# Boost_Controller.net
KiCad netlist of a schematic drawn in EAGLE
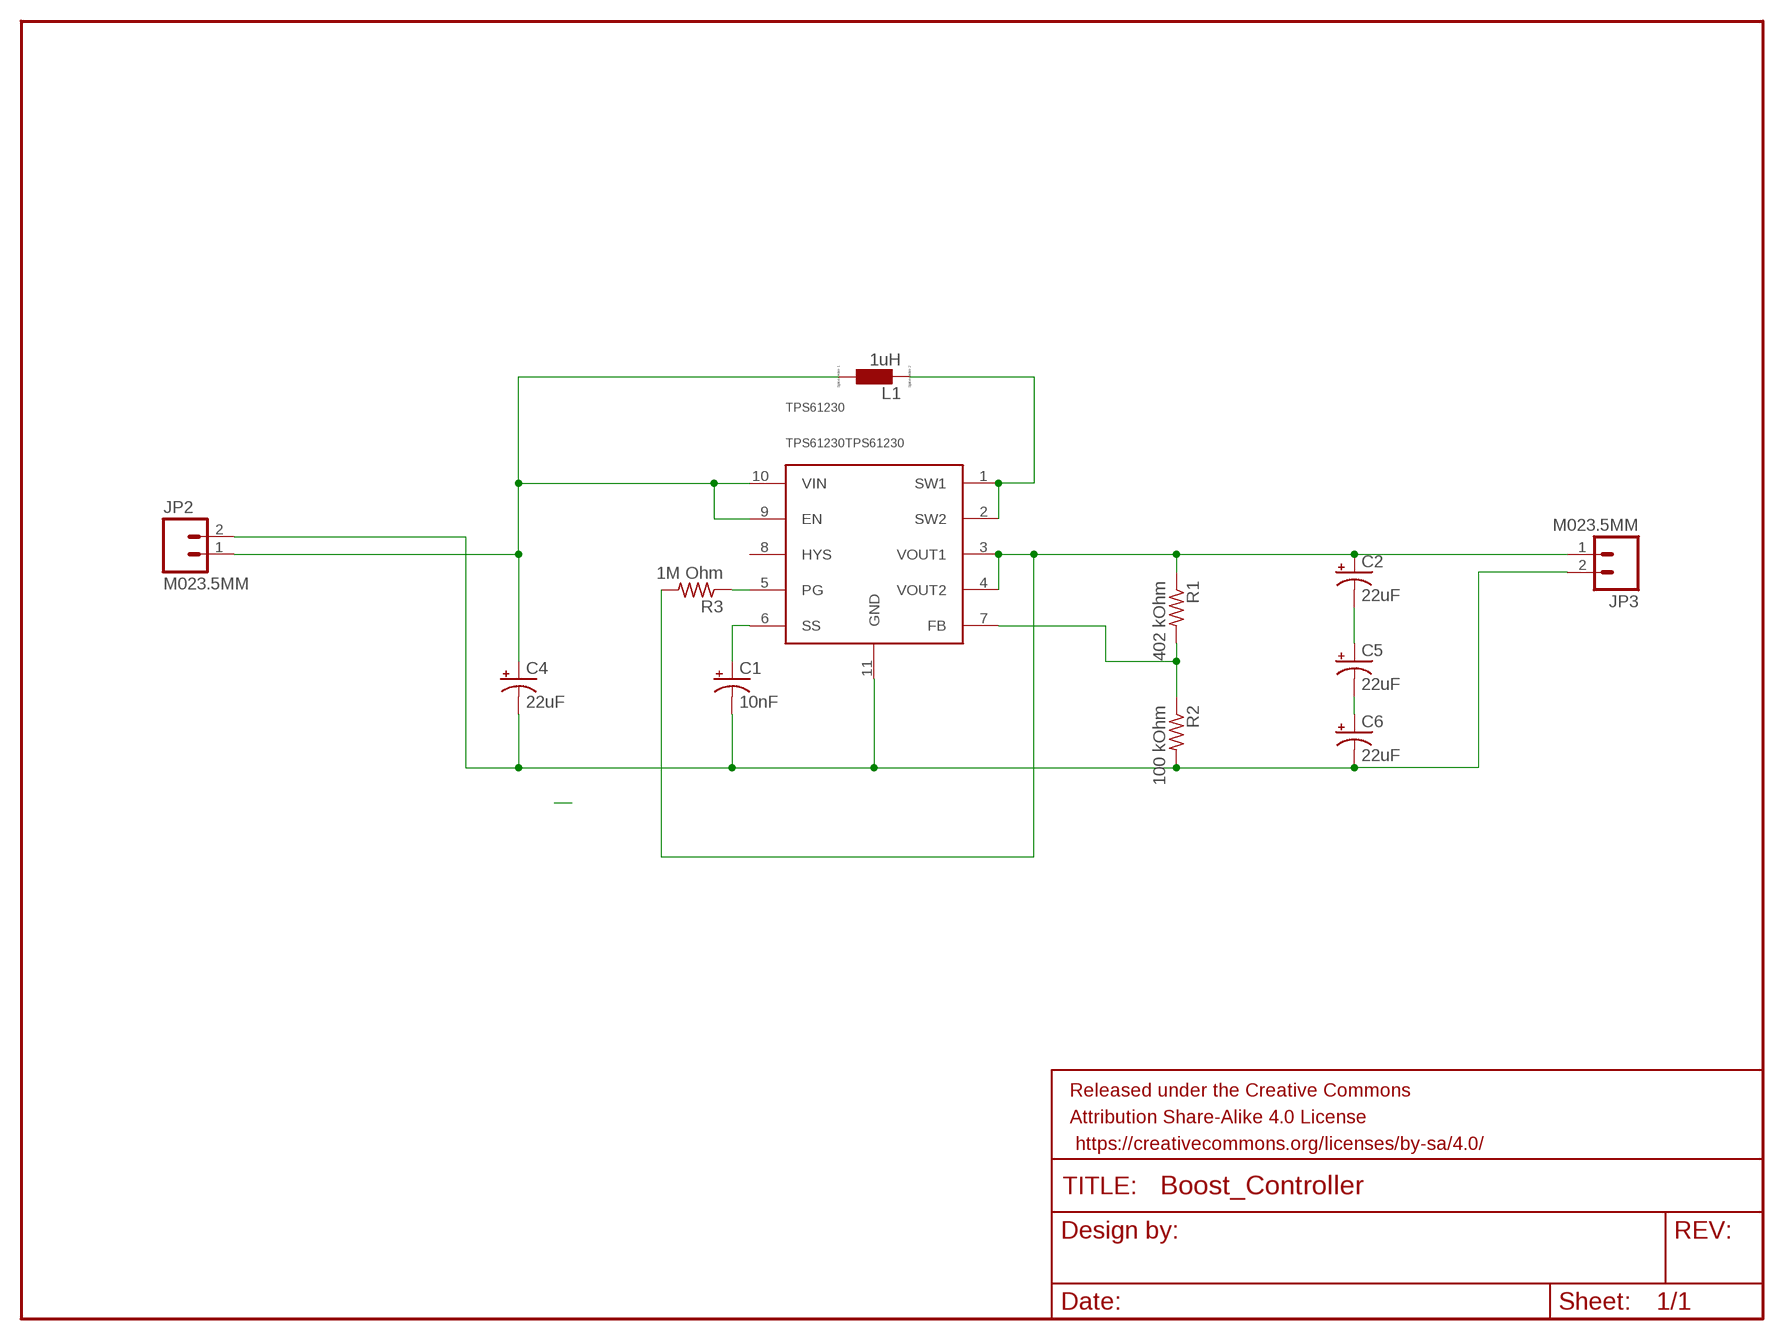
[diagram p0: schematic, sheet 1]

(export (version "E")
  (design (tool "Eeschema 10.0.6"))
  (components
    (comp (ref "C1")
      (value "10nF")
      (footprint "eagle-import:E2,5-5")
      (libsource (lib "eagle-import") (part "CPOL-USE2.5-5"))
    )
    (comp (ref "C2")
      (value "22uF")
      (footprint "eagle-import:E2,5-5")
      (libsource (lib "eagle-import") (part "CPOL-USE2.5-5"))
    )
    (comp (ref "C4")
      (value "22uF")
      (footprint "eagle-import:E2,5-5")
      (libsource (lib "eagle-import") (part "CPOL-USE2.5-5"))
    )
    (comp (ref "C5")
      (value "22uF")
      (footprint "eagle-import:E2,5-5")
      (libsource (lib "eagle-import") (part "CPOL-USE2.5-5"))
    )
    (comp (ref "C6")
      (value "22uF")
      (footprint "eagle-import:E2,5-5")
      (libsource (lib "eagle-import") (part "CPOL-USE2.5-5"))
    )
    (comp (ref "FRAME1")
      (value "FRAME-LETTER")
      (footprint "eagle-import:CREATIVE_COMMONS")
      (libsource (lib "eagle-import") (part "FRAME-LETTER"))
    )
    (comp (ref "JP2")
      (value "M023.5MM")
      (footprint "eagle-import:SCREWTERMINAL-3.5MM-2")
      (libsource (lib "eagle-import") (part "M023.5MM"))
    )
    (comp (ref "JP3")
      (value "M023.5MM")
      (footprint "eagle-import:SCREWTERMINAL-3.5MM-2")
      (libsource (lib "eagle-import") (part "M023.5MM"))
    )
    (comp (ref "L1")
      (value "1uH")
      (footprint "eagle-import:0207_10")
      (libsource (lib "eagle-import") (part "L0207/10"))
    )
    (comp (ref "R1")
      (value "402 kOhm")
      (footprint "eagle-import:0207_10")
      (libsource (lib "eagle-import") (part "R-US_0207/10"))
    )
    (comp (ref "R2")
      (value "100 kOhm")
      (footprint "eagle-import:0207_10")
      (libsource (lib "eagle-import") (part "R-US_0207/10"))
    )
    (comp (ref "R3")
      (value "1M Ohm")
      (footprint "eagle-import:0207_10")
      (libsource (lib "eagle-import") (part "R-US_0207/10"))
    )
    (comp (ref "TPS61230")
      (value "TPS61230TPS61230")
      (footprint "eagle-import:SON50P300X300X100-11N")
      (libsource (lib "eagle-import") (part "TPS61230TPS61230"))
    )
  )
  (nets
    (net (code "1") (name "Net-(C2-Pad-)") (class "Default")
      (node (ref "C2") (pin "-") (pinfunction "-_-") (pintype "passive"))
      (node (ref "C5") (pin "+") (pinfunction "+_+") (pintype "passive"))
    )
    (net (code "2") (name "Net-(C5-Pad-)") (class "Default")
      (node (ref "C5") (pin "-") (pinfunction "-_-") (pintype "passive"))
      (node (ref "C6") (pin "+") (pinfunction "+_+") (pintype "passive"))
    )
    (net (code "3") (name "Net-(TPS61230-EN)") (class "Default")
      (node (ref "C4") (pin "+") (pinfunction "+_+") (pintype "passive"))
      (node (ref "JP2") (pin "1") (pinfunction "1_1") (pintype "passive"))
      (node (ref "L1") (pin "1") (pinfunction "1_1") (pintype "passive"))
      (node (ref "TPS61230") (pin "10") (pinfunction "VIN_10") (pintype "bidirectional"))
      (node (ref "TPS61230") (pin "9") (pinfunction "EN_9") (pintype "bidirectional"))
    )
    (net (code "4") (name "Net-(TPS61230-FB)") (class "Default")
      (node (ref "R1") (pin "2") (pinfunction "2_2") (pintype "passive"))
      (node (ref "R2") (pin "1") (pinfunction "1_1") (pintype "passive"))
      (node (ref "TPS61230") (pin "7") (pinfunction "FB_7") (pintype "bidirectional"))
    )
    (net (code "5") (name "Net-(TPS61230-GND)") (class "Default")
      (node (ref "C1") (pin "-") (pinfunction "-_-") (pintype "passive"))
      (node (ref "C4") (pin "-") (pinfunction "-_-") (pintype "passive"))
      (node (ref "C6") (pin "-") (pinfunction "-_-") (pintype "passive"))
      (node (ref "JP2") (pin "2") (pinfunction "2_2") (pintype "passive"))
      (node (ref "JP3") (pin "2") (pinfunction "2_2") (pintype "passive"))
      (node (ref "R2") (pin "2") (pinfunction "2_2") (pintype "passive"))
      (node (ref "TPS61230") (pin "11") (pinfunction "GND_11") (pintype "bidirectional"))
    )
    (net (code "6") (name "Net-(TPS61230-PG)") (class "Default")
      (node (ref "R3") (pin "1") (pinfunction "1_1") (pintype "passive"))
      (node (ref "TPS61230") (pin "5") (pinfunction "PG_5") (pintype "bidirectional"))
    )
    (net (code "7") (name "Net-(TPS61230-SS)") (class "Default")
      (node (ref "C1") (pin "+") (pinfunction "+_+") (pintype "passive"))
      (node (ref "TPS61230") (pin "6") (pinfunction "SS_6") (pintype "bidirectional"))
    )
    (net (code "8") (name "Net-(TPS61230-SW1)") (class "Default")
      (node (ref "L1") (pin "2") (pinfunction "2_2") (pintype "passive"))
      (node (ref "TPS61230") (pin "1") (pinfunction "SW1_1") (pintype "bidirectional"))
      (node (ref "TPS61230") (pin "2") (pinfunction "SW2_2") (pintype "bidirectional"))
    )
    (net (code "9") (name "Net-(TPS61230-VOUT1)") (class "Default")
      (node (ref "C2") (pin "+") (pinfunction "+_+") (pintype "passive"))
      (node (ref "JP3") (pin "1") (pinfunction "1_1") (pintype "passive"))
      (node (ref "R1") (pin "1") (pinfunction "1_1") (pintype "passive"))
      (node (ref "R3") (pin "2") (pinfunction "2_2") (pintype "passive"))
      (node (ref "TPS61230") (pin "3") (pinfunction "VOUT1_3") (pintype "bidirectional"))
      (node (ref "TPS61230") (pin "4") (pinfunction "VOUT2_4") (pintype "bidirectional"))
    )
    (net (code "10") (name "unconnected-(TPS61230-HYS-Pad8)") (class "Default")
      (node (ref "TPS61230") (pin "8") (pinfunction "HYS_8") (pintype "bidirectional"))
    )
  )
)
